# merope-central.net
KiCad netlist of a schematic drawn in EAGLE
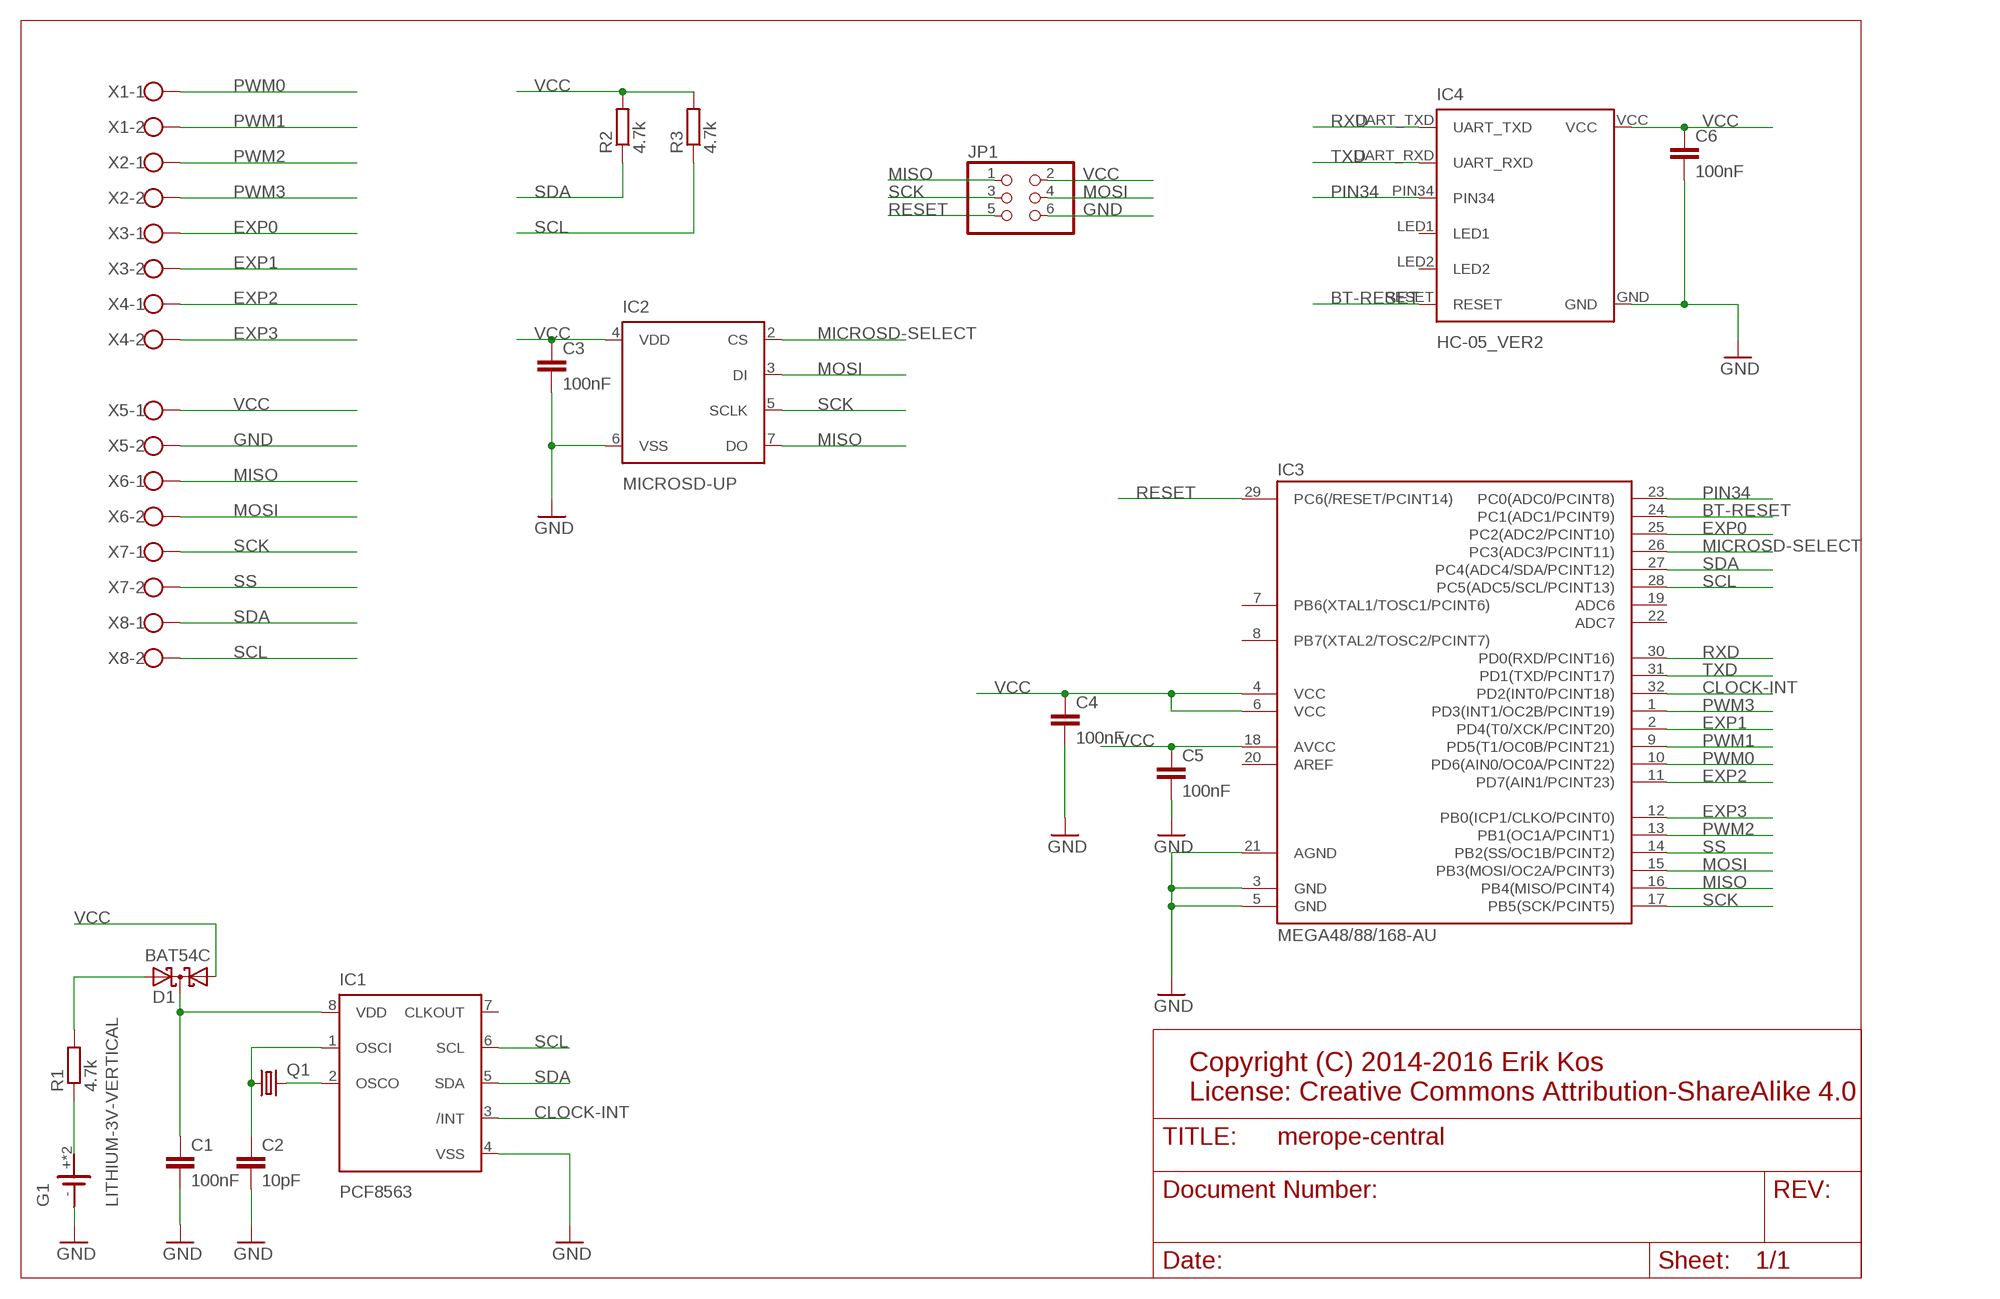
[diagram p0: schematic, sheet 1]

(export (version "E")
  (design (tool "Eeschema 10.0.6"))
  (components
    (comp (ref "C1")
      (value "100nF")
      (footprint "eagle-import:C0805")
      (libsource (lib "eagle-import") (part "C-EUC0805"))
    )
    (comp (ref "C2")
      (value "10pF")
      (footprint "eagle-import:C0805")
      (libsource (lib "eagle-import") (part "C-EUC0805"))
    )
    (comp (ref "C3")
      (value "100nF")
      (footprint "eagle-import:C0805")
      (libsource (lib "eagle-import") (part "C-EUC0805"))
    )
    (comp (ref "C4")
      (value "100nF")
      (footprint "eagle-import:C0805")
      (libsource (lib "eagle-import") (part "C-EUC0805"))
    )
    (comp (ref "C5")
      (value "100nF")
      (footprint "eagle-import:C0805")
      (libsource (lib "eagle-import") (part "C-EUC0805"))
    )
    (comp (ref "C6")
      (value "100nF")
      (footprint "eagle-import:C0805")
      (libsource (lib "eagle-import") (part "C-EUC0805"))
    )
    (comp (ref "D1")
      (value "BAT54C")
      (footprint "eagle-import:SOT23")
      (libsource (lib "eagle-import") (part "BAT54C"))
    )
    (comp (ref "G1")
      (value "LITHIUM-3V-VERTICAL")
      (footprint "eagle-import:LITHIUM-3V-VERTICAL")
      (libsource (lib "eagle-import") (part "LITHIUM-3V-VERTICAL"))
    )
    (comp (ref "IC1")
      (value "PCF8563")
      (footprint "eagle-import:SO8")
      (libsource (lib "eagle-import") (part "PCF8563"))
    )
    (comp (ref "IC2")
      (value "MICROSD-UP")
      (footprint "eagle-import:MICROSD-UP")
      (libsource (lib "eagle-import") (part "MICROSD-UP"))
    )
    (comp (ref "IC3")
      (value "MEGA48/88/168-AU")
      (footprint "eagle-import:TQFP32-08")
      (libsource (lib "eagle-import") (part "MEGA48/88/168-AU"))
    )
    (comp (ref "IC4")
      (value "HC-05_VER2")
      (footprint "eagle-import:HC-05_VER2")
      (libsource (lib "eagle-import") (part "HC-05_VER2"))
    )
    (comp (ref "JP1")
      (value "PINHD-2X3")
      (footprint "eagle-import:2X03")
      (libsource (lib "eagle-import") (part "PINHD-2X3"))
    )
    (comp (ref "Q1")
      (value "CRYSTALTC26V")
      (footprint "eagle-import:TC26V")
      (libsource (lib "eagle-import") (part "CRYSTALTC26V"))
    )
    (comp (ref "R1")
      (value "4.7k")
      (footprint "eagle-import:M0805")
      (libsource (lib "eagle-import") (part "R-EU_M0805"))
    )
    (comp (ref "R2")
      (value "4.7k")
      (footprint "eagle-import:M0805")
      (libsource (lib "eagle-import") (part "R-EU_M0805"))
    )
    (comp (ref "R3")
      (value "4.7k")
      (footprint "eagle-import:M0805")
      (libsource (lib "eagle-import") (part "R-EU_M0805"))
    )
    (comp (ref "X1")
      (value "TERMINAL_BLOCK_35_2")
      (footprint "eagle-import:TERMINAL_BLOCK_35_2")
      (libsource (lib "eagle-import") (part "TERMINAL_BLOCK_35_2"))
    )
    (comp (ref "X2")
      (value "TERMINAL_BLOCK_35_2")
      (footprint "eagle-import:TERMINAL_BLOCK_35_2")
      (libsource (lib "eagle-import") (part "TERMINAL_BLOCK_35_2"))
    )
    (comp (ref "X3")
      (value "TERMINAL_BLOCK_35_2")
      (footprint "eagle-import:TERMINAL_BLOCK_35_2")
      (libsource (lib "eagle-import") (part "TERMINAL_BLOCK_35_2"))
    )
    (comp (ref "X4")
      (value "TERMINAL_BLOCK_35_2")
      (footprint "eagle-import:TERMINAL_BLOCK_35_2")
      (libsource (lib "eagle-import") (part "TERMINAL_BLOCK_35_2"))
    )
    (comp (ref "X5")
      (value "TERMINAL_BLOCK_35_2")
      (footprint "eagle-import:TERMINAL_BLOCK_35_2")
      (libsource (lib "eagle-import") (part "TERMINAL_BLOCK_35_2"))
    )
    (comp (ref "X6")
      (value "TERMINAL_BLOCK_35_2")
      (footprint "eagle-import:TERMINAL_BLOCK_35_2")
      (libsource (lib "eagle-import") (part "TERMINAL_BLOCK_35_2"))
    )
    (comp (ref "X7")
      (value "TERMINAL_BLOCK_35_2")
      (footprint "eagle-import:TERMINAL_BLOCK_35_2")
      (libsource (lib "eagle-import") (part "TERMINAL_BLOCK_35_2"))
    )
    (comp (ref "X8")
      (value "TERMINAL_BLOCK_35_2")
      (footprint "eagle-import:TERMINAL_BLOCK_35_2")
      (libsource (lib "eagle-import") (part "TERMINAL_BLOCK_35_2"))
    )
  )
  (nets
    (net (code "1") (name "/BT-RESET") (class "Default")
      (node (ref "IC3") (pin "24") (pinfunction "PC1(ADC1/PCINT9)_24") (pintype "bidirectional"))
      (node (ref "IC4") (pin "RESET") (pinfunction "RESET_RESET") (pintype "input"))
    )
    (net (code "2") (name "/CLOCK-INT") (class "Default")
      (node (ref "IC1") (pin "3") (pinfunction "/INT_3") (pintype "input"))
      (node (ref "IC3") (pin "32") (pinfunction "PD2(INT0/PCINT18)_32") (pintype "bidirectional"))
    )
    (net (code "3") (name "/EXP0") (class "Default")
      (node (ref "IC3") (pin "25") (pinfunction "PC2(ADC2/PCINT10)_25") (pintype "bidirectional"))
      (node (ref "X3") (pin "1") (pinfunction "KL_1") (pintype "passive"))
    )
    (net (code "4") (name "/EXP1") (class "Default")
      (node (ref "IC3") (pin "2") (pinfunction "PD4(T0/XCK/PCINT20)_2") (pintype "bidirectional"))
      (node (ref "X3") (pin "2") (pinfunction "KL_2") (pintype "passive"))
    )
    (net (code "5") (name "/EXP2") (class "Default")
      (node (ref "IC3") (pin "11") (pinfunction "PD7(AIN1/PCINT23)_11") (pintype "bidirectional"))
      (node (ref "X4") (pin "1") (pinfunction "KL_1") (pintype "passive"))
    )
    (net (code "6") (name "/EXP3") (class "Default")
      (node (ref "IC3") (pin "12") (pinfunction "PB0(ICP1/CLKO/PCINT0)_12") (pintype "bidirectional"))
      (node (ref "X4") (pin "2") (pinfunction "KL_2") (pintype "passive"))
    )
    (net (code "7") (name "/MICROSD-SELECT") (class "Default")
      (node (ref "IC2") (pin "2") (pinfunction "CS_2") (pintype "output"))
      (node (ref "IC3") (pin "26") (pinfunction "PC3(ADC3/PCINT11)_26") (pintype "bidirectional"))
    )
    (net (code "8") (name "/MISO") (class "Default")
      (node (ref "IC2") (pin "7") (pinfunction "DO_7") (pintype "input"))
      (node (ref "IC3") (pin "16") (pinfunction "PB4(MISO/PCINT4)_16") (pintype "bidirectional"))
      (node (ref "JP1") (pin "1") (pinfunction "1_1") (pintype "passive"))
      (node (ref "X6") (pin "1") (pinfunction "KL_1") (pintype "passive"))
    )
    (net (code "9") (name "/MOSI") (class "Default")
      (node (ref "IC2") (pin "3") (pinfunction "DI_3") (pintype "input"))
      (node (ref "IC3") (pin "15") (pinfunction "PB3(MOSI/OC2A/PCINT3)_15") (pintype "bidirectional"))
      (node (ref "JP1") (pin "4") (pinfunction "4_4") (pintype "passive"))
      (node (ref "X6") (pin "2") (pinfunction "KL_2") (pintype "passive"))
    )
    (net (code "10") (name "/PIN34") (class "Default")
      (node (ref "IC3") (pin "23") (pinfunction "PC0(ADC0/PCINT8)_23") (pintype "bidirectional"))
      (node (ref "IC4") (pin "PIN34") (pinfunction "PIN34_PIN34") (pintype "input"))
    )
    (net (code "11") (name "/PWM0") (class "Default")
      (node (ref "IC3") (pin "10") (pinfunction "PD6(AIN0/OC0A/PCINT22)_10") (pintype "bidirectional"))
      (node (ref "X1") (pin "1") (pinfunction "KL_1") (pintype "passive"))
    )
    (net (code "12") (name "/PWM1") (class "Default")
      (node (ref "IC3") (pin "9") (pinfunction "PD5(T1/OC0B/PCINT21)_9") (pintype "bidirectional"))
      (node (ref "X1") (pin "2") (pinfunction "KL_2") (pintype "passive"))
    )
    (net (code "13") (name "/PWM2") (class "Default")
      (node (ref "IC3") (pin "13") (pinfunction "PB1(OC1A/PCINT1)_13") (pintype "bidirectional"))
      (node (ref "X2") (pin "1") (pinfunction "KL_1") (pintype "passive"))
    )
    (net (code "14") (name "/PWM3") (class "Default")
      (node (ref "IC3") (pin "1") (pinfunction "PD3(INT1/OC2B/PCINT19)_1") (pintype "bidirectional"))
      (node (ref "X2") (pin "2") (pinfunction "KL_2") (pintype "passive"))
    )
    (net (code "15") (name "/RESET") (class "Default")
      (node (ref "IC3") (pin "29") (pinfunction "PC6(/RESET/PCINT14)_29") (pintype "bidirectional"))
      (node (ref "JP1") (pin "5") (pinfunction "5_5") (pintype "passive"))
    )
    (net (code "16") (name "/RXD") (class "Default")
      (node (ref "IC3") (pin "30") (pinfunction "PD0(RXD/PCINT16)_30") (pintype "bidirectional"))
      (node (ref "IC4") (pin "UART_TXD") (pinfunction "UART_TXD_UART_TXD") (pintype "output"))
    )
    (net (code "17") (name "/SCK") (class "Default")
      (node (ref "IC2") (pin "5") (pinfunction "SCLK_5") (pintype "bidirectional"))
      (node (ref "IC3") (pin "17") (pinfunction "PB5(SCK/PCINT5)_17") (pintype "bidirectional"))
      (node (ref "JP1") (pin "3") (pinfunction "3_3") (pintype "passive"))
      (node (ref "X7") (pin "1") (pinfunction "KL_1") (pintype "passive"))
    )
    (net (code "18") (name "/SCL") (class "Default")
      (node (ref "IC1") (pin "6") (pinfunction "SCL_6") (pintype "input"))
      (node (ref "IC3") (pin "28") (pinfunction "PC5(ADC5/SCL/PCINT13)_28") (pintype "bidirectional"))
      (node (ref "R3") (pin "1") (pinfunction "1_1") (pintype "passive"))
      (node (ref "X8") (pin "2") (pinfunction "KL_2") (pintype "passive"))
    )
    (net (code "19") (name "/SDA") (class "Default")
      (node (ref "IC1") (pin "5") (pinfunction "SDA_5") (pintype "bidirectional"))
      (node (ref "IC3") (pin "27") (pinfunction "PC4(ADC4/SDA/PCINT12)_27") (pintype "bidirectional"))
      (node (ref "R2") (pin "1") (pinfunction "1_1") (pintype "passive"))
      (node (ref "X8") (pin "1") (pinfunction "KL_1") (pintype "passive"))
    )
    (net (code "20") (name "/SS") (class "Default")
      (node (ref "IC3") (pin "14") (pinfunction "PB2(SS/OC1B/PCINT2)_14") (pintype "bidirectional"))
      (node (ref "X7") (pin "2") (pinfunction "KL_2") (pintype "passive"))
    )
    (net (code "21") (name "/TXD") (class "Default")
      (node (ref "IC3") (pin "31") (pinfunction "PD1(TXD/PCINT17)_31") (pintype "bidirectional"))
      (node (ref "IC4") (pin "UART_RXD") (pinfunction "UART_RXD_UART_RXD") (pintype "input"))
    )
    (net (code "22") (name "/VCC") (class "Default")
      (node (ref "C3") (pin "1") (pinfunction "1_1") (pintype "passive"))
      (node (ref "C4") (pin "1") (pinfunction "1_1") (pintype "passive"))
      (node (ref "C5") (pin "1") (pinfunction "1_1") (pintype "passive"))
      (node (ref "C6") (pin "1") (pinfunction "1_1") (pintype "passive"))
      (node (ref "D1") (pin "1") (pinfunction "A1_1") (pintype "passive"))
      (node (ref "IC2") (pin "4") (pinfunction "VDD_4") (pintype "power_in"))
      (node (ref "IC3") (pin "18") (pinfunction "AVCC_18") (pintype "passive"))
      (node (ref "IC3") (pin "4") (pinfunction "VCC_4") (pintype "power_in"))
      (node (ref "IC3") (pin "6") (pinfunction "VCC_6") (pintype "power_in"))
      (node (ref "IC4") (pin "VCC") (pinfunction "VCC_VCC") (pintype "power_in"))
      (node (ref "JP1") (pin "2") (pinfunction "2_2") (pintype "passive"))
      (node (ref "R2") (pin "2") (pinfunction "2_2") (pintype "passive"))
      (node (ref "R3") (pin "2") (pinfunction "2_2") (pintype "passive"))
      (node (ref "X5") (pin "1") (pinfunction "KL_1") (pintype "passive"))
    )
    (net (code "23") (name "GND") (class "Default")
      (node (ref "C1") (pin "2") (pinfunction "2_2") (pintype "passive"))
      (node (ref "C2") (pin "2") (pinfunction "2_2") (pintype "passive"))
      (node (ref "C3") (pin "2") (pinfunction "2_2") (pintype "passive"))
      (node (ref "C4") (pin "2") (pinfunction "2_2") (pintype "passive"))
      (node (ref "C5") (pin "2") (pinfunction "2_2") (pintype "passive"))
      (node (ref "C6") (pin "2") (pinfunction "2_2") (pintype "passive"))
      (node (ref "G1") (pin "-") (pinfunction "-_-") (pintype "bidirectional"))
      (node (ref "IC1") (pin "4") (pinfunction "VSS_4") (pintype "power_in"))
      (node (ref "IC2") (pin "6") (pinfunction "VSS_6") (pintype "power_in"))
      (node (ref "IC3") (pin "21") (pinfunction "AGND_21") (pintype "power_in"))
      (node (ref "IC3") (pin "3") (pinfunction "GND_3") (pintype "power_in"))
      (node (ref "IC3") (pin "5") (pinfunction "GND_5") (pintype "power_in"))
      (node (ref "IC4") (pin "GND") (pinfunction "GND_GND") (pintype "power_in"))
      (node (ref "JP1") (pin "6") (pinfunction "6_6") (pintype "passive"))
      (node (ref "X5") (pin "2") (pinfunction "KL_2") (pintype "passive"))
    )
    (net (code "24") (name "Net-(D1-A2)") (class "Default")
      (node (ref "D1") (pin "2") (pinfunction "A2_2") (pintype "passive"))
      (node (ref "R1") (pin "2") (pinfunction "2_2") (pintype "passive"))
    )
    (net (code "25") (name "Net-(D1-CC)") (class "Default")
      (node (ref "C1") (pin "1") (pinfunction "1_1") (pintype "passive"))
      (node (ref "D1") (pin "3") (pinfunction "CC_3") (pintype "passive"))
      (node (ref "IC1") (pin "8") (pinfunction "VDD_8") (pintype "power_in"))
    )
    (net (code "26") (name "Net-(G1-+-Pad+1)") (class "Default")
      (node (ref "G1") (pin "+") (pinfunction "+_+") (pintype "bidirectional"))
      (node (ref "G1") (pin "+1") (pinfunction "+_+1") (pintype "bidirectional"))
      (node (ref "R1") (pin "1") (pinfunction "1_1") (pintype "passive"))
    )
    (net (code "27") (name "Net-(IC1-OSCI)") (class "Default")
      (node (ref "C2") (pin "1") (pinfunction "1_1") (pintype "passive"))
      (node (ref "IC1") (pin "1") (pinfunction "OSCI_1") (pintype "input"))
      (node (ref "Q1") (pin "1") (pinfunction "1_1") (pintype "passive"))
    )
    (net (code "28") (name "Net-(IC1-OSCO)") (class "Default")
      (node (ref "IC1") (pin "2") (pinfunction "OSCO_2") (pintype "output"))
      (node (ref "Q1") (pin "2") (pinfunction "2_2") (pintype "passive"))
    )
    (net (code "29") (name "unconnected-(IC1-CLKOUT-Pad7)") (class "Default")
      (node (ref "IC1") (pin "7") (pinfunction "CLKOUT_7") (pintype "output"))
    )
    (net (code "30") (name "unconnected-(IC3-ADC6-Pad19)") (class "Default")
      (node (ref "IC3") (pin "19") (pinfunction "ADC6_19") (pintype "passive"))
    )
    (net (code "31") (name "unconnected-(IC3-ADC7-Pad22)") (class "Default")
      (node (ref "IC3") (pin "22") (pinfunction "ADC7_22") (pintype "passive"))
    )
    (net (code "32") (name "unconnected-(IC3-AREF-Pad20)") (class "Default")
      (node (ref "IC3") (pin "20") (pinfunction "AREF_20") (pintype "passive"))
    )
    (net (code "33") (name "unconnected-(IC3-PB6(XTAL1{slash}TOSC1{slash}PCINT6)-Pad7)") (class "Default")
      (node (ref "IC3") (pin "7") (pinfunction "PB6(XTAL1/TOSC1/PCINT6)_7") (pintype "bidirectional"))
    )
    (net (code "34") (name "unconnected-(IC3-PB7(XTAL2{slash}TOSC2{slash}PCINT7)-Pad8)") (class "Default")
      (node (ref "IC3") (pin "8") (pinfunction "PB7(XTAL2/TOSC2/PCINT7)_8") (pintype "bidirectional"))
    )
    (net (code "35") (name "unconnected-(IC4-PadLED1)") (class "Default")
      (node (ref "IC4") (pin "LED1") (pinfunction "LED1_LED1") (pintype "input"))
    )
    (net (code "36") (name "unconnected-(IC4-PadLED2)") (class "Default")
      (node (ref "IC4") (pin "LED2") (pinfunction "LED2_LED2") (pintype "input"))
    )
  )
)
